# MAX5214.net
KiCad netlist of a schematic drawn in EAGLE
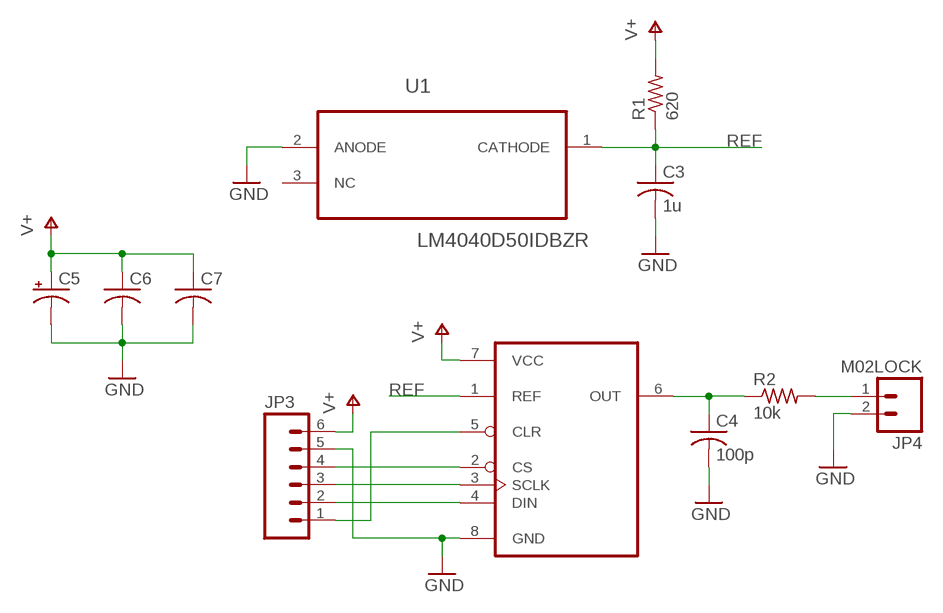
[diagram p0: schematic, sheet 2]

(export (version "E")
  (design (tool "Eeschema 10.0.6"))
  (components
    (comp (ref "C3")
      (value "1u")
      (footprint "eagle-import:C0805")
      (libsource (lib "eagle-import") (part "C-USC0805"))
    )
    (comp (ref "C4")
      (value "100p")
      (footprint "eagle-import:C0805")
      (libsource (lib "eagle-import") (part "C-USC0805"))
    )
    (comp (ref "C5")
      (value "CPOL-US")
      (footprint "eagle-import:SMD_6.6X6.6")
      (libsource (lib "eagle-import") (part "CPOL-US"))
    )
    (comp (ref "C6")
      (value "C-USC0805")
      (footprint "eagle-import:C0805")
      (libsource (lib "eagle-import") (part "C-USC0805"))
    )
    (comp (ref "C7")
      (value "C-USC0805")
      (footprint "eagle-import:C0805")
      (libsource (lib "eagle-import") (part "C-USC0805"))
    )
    (comp (ref "JP3")
      (value "M06LOCK")
      (footprint "eagle-import:1X06_LOCK")
      (libsource (lib "eagle-import") (part "M06LOCK"))
    )
    (comp (ref "JP4")
      (value "M02LOCK")
      (footprint "eagle-import:1X02_LOCK")
      (libsource (lib "eagle-import") (part "M02LOCK"))
    )
    (comp (ref "R1")
      (value "620")
      (footprint "eagle-import:R0805")
      (libsource (lib "eagle-import") (part "R-US_R0805"))
    )
    (comp (ref "R2")
      (value "10k")
      (footprint "eagle-import:R0805")
      (libsource (lib "eagle-import") (part "R-US_R0805"))
    )
    (comp (ref "U$2")
      (value "MAX5214")
      (footprint "eagle-import:UMAX8")
      (libsource (lib "eagle-import") (part "MAX5214"))
    )
    (comp (ref "U1")
      (value "LM4040D50IDBZR")
      (footprint "eagle-import:SOT95P237X112-3N")
      (libsource (lib "eagle-import") (part "LM4040D50IDBZR"))
    )
  )
  (nets
    (net (code "1") (name "GND") (class "Default")
      (node (ref "C3") (pin "2") (pinfunction "2_2") (pintype "passive"))
      (node (ref "C4") (pin "2") (pinfunction "2_2") (pintype "passive"))
      (node (ref "C5") (pin "-") (pinfunction "-_-") (pintype "passive"))
      (node (ref "C6") (pin "2") (pinfunction "2_2") (pintype "passive"))
      (node (ref "C7") (pin "2") (pinfunction "2_2") (pintype "passive"))
      (node (ref "JP3") (pin "5") (pinfunction "5_5") (pintype "passive"))
      (node (ref "JP4") (pin "2") (pinfunction "2_2") (pintype "passive"))
      (node (ref "U$2") (pin "8") (pinfunction "GND_8") (pintype "power_in"))
      (node (ref "U1") (pin "2") (pinfunction "ANODE_2") (pintype "input"))
    )
    (net (code "2") (name "Net-(JP4-Pad1)") (class "Default")
      (node (ref "JP4") (pin "1") (pinfunction "1_1") (pintype "passive"))
      (node (ref "R2") (pin "2") (pinfunction "2_2") (pintype "passive"))
    )
    (net (code "3") (name "Net-(U$2-CLR)") (class "Default")
      (node (ref "JP3") (pin "1") (pinfunction "1_1") (pintype "passive"))
      (node (ref "U$2") (pin "5") (pinfunction "CLR_5") (pintype "input"))
    )
    (net (code "4") (name "Net-(U$2-CS)") (class "Default")
      (node (ref "JP3") (pin "4") (pinfunction "4_4") (pintype "passive"))
      (node (ref "U$2") (pin "2") (pinfunction "CS_2") (pintype "input"))
    )
    (net (code "5") (name "Net-(U$2-DIN)") (class "Default")
      (node (ref "JP3") (pin "2") (pinfunction "2_2") (pintype "passive"))
      (node (ref "U$2") (pin "4") (pinfunction "DIN_4") (pintype "input"))
    )
    (net (code "6") (name "Net-(U$2-OUT)") (class "Default")
      (node (ref "C4") (pin "1") (pinfunction "1_1") (pintype "passive"))
      (node (ref "R2") (pin "1") (pinfunction "1_1") (pintype "passive"))
      (node (ref "U$2") (pin "6") (pinfunction "OUT_6") (pintype "bidirectional"))
    )
    (net (code "7") (name "Net-(U$2-SCLK)") (class "Default")
      (node (ref "JP3") (pin "3") (pinfunction "3_3") (pintype "passive"))
      (node (ref "U$2") (pin "3") (pinfunction "SCLK_3") (pintype "input"))
    )
    (net (code "8") (name "REF") (class "Default")
      (node (ref "C3") (pin "1") (pinfunction "1_1") (pintype "passive"))
      (node (ref "R1") (pin "1") (pinfunction "1_1") (pintype "passive"))
      (node (ref "U$2") (pin "1") (pinfunction "REF_1") (pintype "input"))
      (node (ref "U1") (pin "1") (pinfunction "CATHODE_1") (pintype "output"))
    )
    (net (code "9") (name "V+") (class "Default")
      (node (ref "C5") (pin "+") (pinfunction "+_+") (pintype "passive"))
      (node (ref "C6") (pin "1") (pinfunction "1_1") (pintype "passive"))
      (node (ref "C7") (pin "1") (pinfunction "1_1") (pintype "passive"))
      (node (ref "JP3") (pin "6") (pinfunction "6_6") (pintype "passive"))
      (node (ref "R1") (pin "2") (pinfunction "2_2") (pintype "passive"))
      (node (ref "U$2") (pin "7") (pinfunction "VCC_7") (pintype "power_in"))
    )
    (net (code "10") (name "unconnected-(U1-NC-Pad3)") (class "Default")
      (node (ref "U1") (pin "3") (pinfunction "NC_3") (pintype "no_connect"))
    )
  )
)
